# SCH_USB-Hub-with-audio-card_2025-04-09_1.net
KiCad netlist of a schematic drawn in EasyEDA
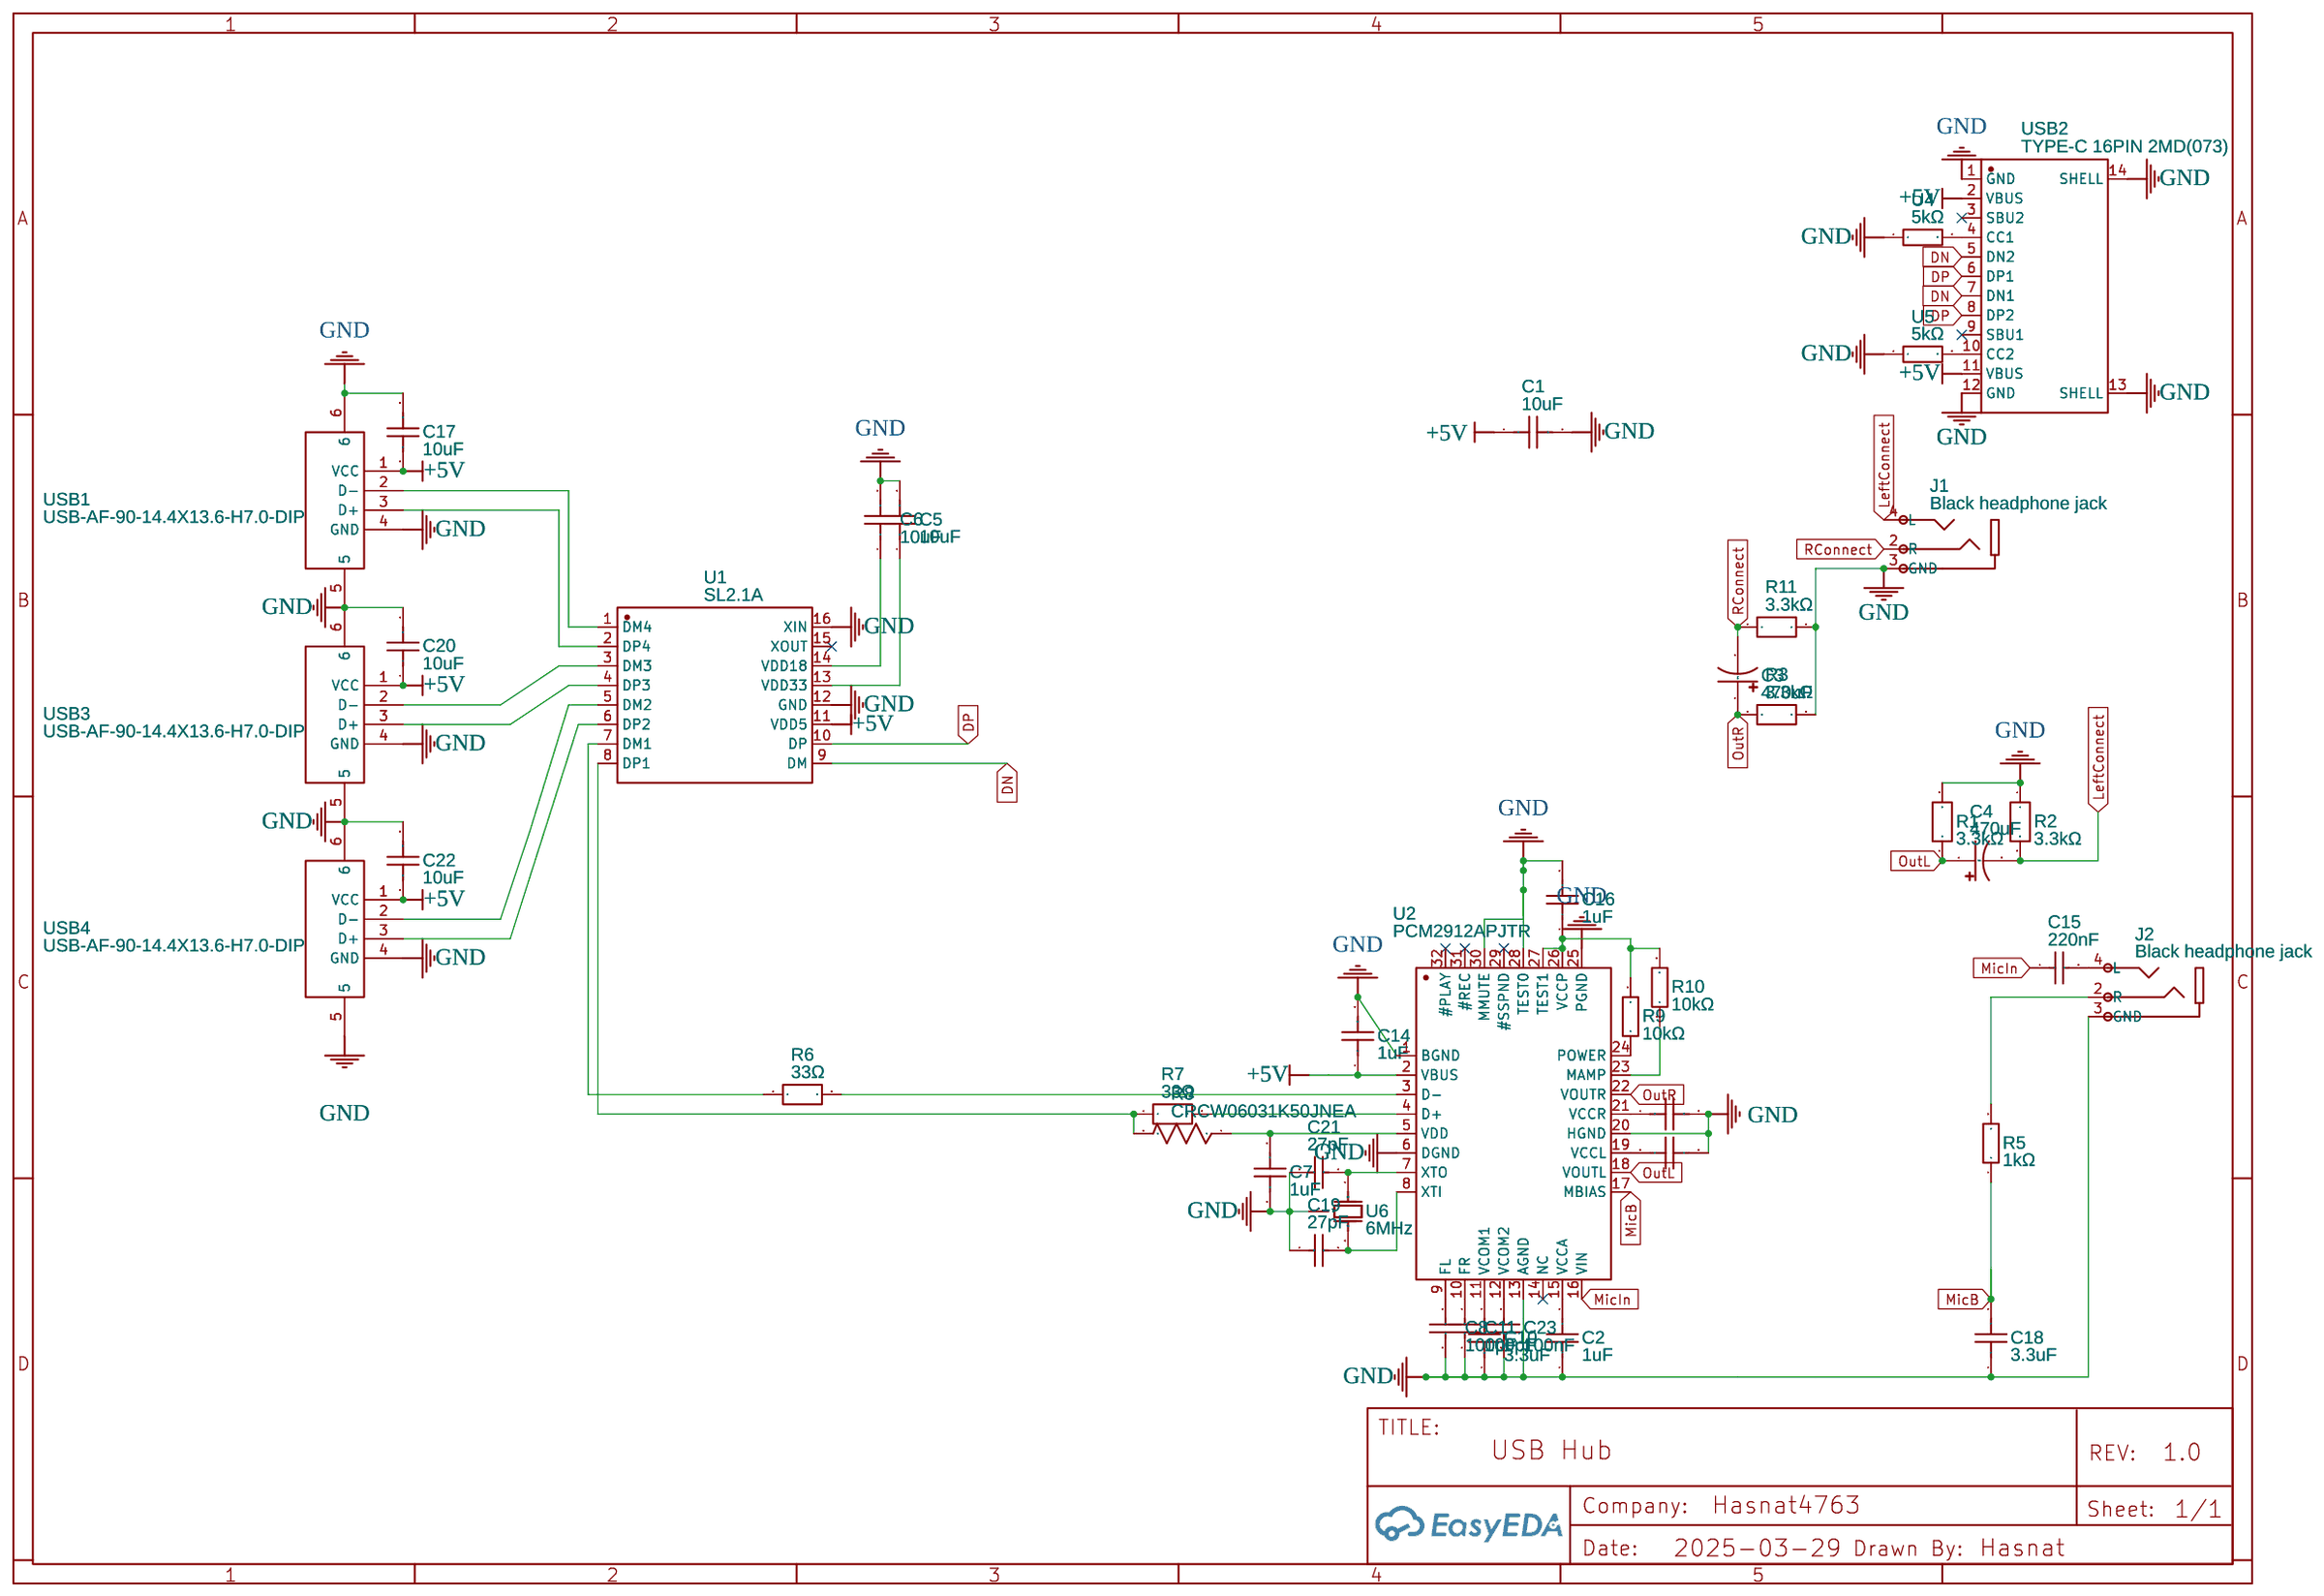
[diagram p0: schematic sheet]

(export (version "E")
  (design (tool "Eeschema 10.0.6"))
  (components
    (comp (ref "C1")
      (value "10uF")
      (fields
        (field (name "Manufacturer Part") "CL10A106KP8NNNC")
        (field (name "Manufacturer") "SAMSUNG(三星)")
      )
      (libsource (lib "") (part "CL10A106KP8NNNC_1"))
    )
    (comp (ref "C2")
      (value "1uF")
      (fields (field (name "Manufacturer Part") "CGB3B1X7R1A105K055AC") (field (name "Manufacturer") "TDK"))
      (libsource (lib "") (part "CGB3B1X7R1A105K055AC"))
    )
    (comp (ref "C3")
      (value "470uF")
      (fields (field (name "Manufacturer Part") "UKW1C471MPD") (field (name "Manufacturer") "Nichicon(尼吉康)"))
      (libsource (lib "") (part "UKW1C471MPD_1"))
    )
    (comp (ref "C4")
      (value "470uF")
      (fields (field (name "Manufacturer Part") "UKW1C471MPD") (field (name "Manufacturer") "Nichicon(尼吉康)"))
      (libsource (lib "") (part "UKW1C471MPD"))
    )
    (comp (ref "C5")
      (value "10uF")
      (fields
        (field (name "Manufacturer Part") "CL10A106KP8NNNC")
        (field (name "Manufacturer") "SAMSUNG(三星)")
      )
      (libsource (lib "") (part "CL10A106KP8NNNC"))
    )
    (comp (ref "C6")
      (value "10uF")
      (fields
        (field (name "Manufacturer Part") "CL10A106KP8NNNC")
        (field (name "Manufacturer") "SAMSUNG(三星)")
      )
      (libsource (lib "") (part "CL10A106KP8NNNC"))
    )
    (comp (ref "C7")
      (value "1uF")
      (fields
        (field (name "Manufacturer Part") "CL31B105KBHNNNE")
        (field (name "Manufacturer") "SAMSUNG(三星)")
      )
      (libsource (lib "") (part "CL31B105KBHNNNE"))
    )
    (comp (ref "C8")
      (value "100pF")
      (fields
        (field (name "Manufacturer Part") "GRM1885C1H101JA01D")
        (field (name "Manufacturer") "muRata(村田)")
      )
      (libsource (lib "") (part "GRM1885C1H101JA01D"))
    )
    (comp (ref "C10")
      (value "3.3uF")
      (fields
        (field (name "Manufacturer Part") "GRM21BR71C335KA73L")
        (field (name "Manufacturer") "muRata(村田)")
      )
      (libsource (lib "") (part "GRM21BR71C335KA73L"))
    )
    (comp (ref "C11")
      (value "100pF")
      (fields
        (field (name "Manufacturer Part") "GRM1885C1H101JA01D")
        (field (name "Manufacturer") "muRata(村田)")
      )
      (libsource (lib "") (part "GRM1885C1H101JA01D"))
    )
    (comp (ref "C12")
      (value "1uF")
      (fields
        (field (name "Manufacturer Part") "CL31B105KBHNNNE")
        (field (name "Manufacturer") "SAMSUNG(三星)")
      )
      (libsource (lib "") (part "CL31B105KBHNNNE_1"))
    )
    (comp (ref "C13")
      (value "1uF")
      (fields
        (field (name "Manufacturer Part") "CL31B105KBHNNNE")
        (field (name "Manufacturer") "SAMSUNG(三星)")
      )
      (libsource (lib "") (part "CL31B105KBHNNNE_1"))
    )
    (comp (ref "C14")
      (value "1uF")
      (fields (field (name "Manufacturer Part") "CGB3B1X7R1A105K055AC") (field (name "Manufacturer") "TDK"))
      (libsource (lib "") (part "CGB3B1X7R1A105K055AC"))
    )
    (comp (ref "C15")
      (value "220nF")
      (fields
        (field (name "Manufacturer Part") "CL05A224KA5NNNC")
        (field (name "Manufacturer") "SAMSUNG(三星)")
      )
      (libsource (lib "") (part "CL05A224KA5NNNC"))
    )
    (comp (ref "C16")
      (value "1uF")
      (fields
        (field (name "Manufacturer Part") "CL31B105KBHNNNE")
        (field (name "Manufacturer") "SAMSUNG(三星)")
      )
      (libsource (lib "") (part "CL31B105KBHNNNE"))
    )
    (comp (ref "C17")
      (value "10uF")
      (fields
        (field (name "Manufacturer Part") "CL10A106KP8NNNC")
        (field (name "Manufacturer") "SAMSUNG(三星)")
      )
      (libsource (lib "") (part "CL10A106KP8NNNC"))
    )
    (comp (ref "C18")
      (value "3.3uF")
      (fields
        (field (name "Manufacturer Part") "KVD500L335M55A0T00")
        (field (name "Manufacturer") "NCC(日本贵弥功)")
      )
      (libsource (lib "") (part "KVD500L335M55A0T00"))
    )
    (comp (ref "C19")
      (value "27pF")
      (fields
        (field (name "Manufacturer Part") "CC0805JRNPO9BN270")
        (field (name "Manufacturer") "YAGEO(国巨)")
      )
      (libsource (lib "") (part "CC0805JRNPO9BN270"))
    )
    (comp (ref "C20")
      (value "10uF")
      (fields
        (field (name "Manufacturer Part") "CL10A106KP8NNNC")
        (field (name "Manufacturer") "SAMSUNG(三星)")
      )
      (libsource (lib "") (part "CL10A106KP8NNNC"))
    )
    (comp (ref "C21")
      (value "27pF")
      (fields
        (field (name "Manufacturer Part") "CC0805JRNPO9BN270")
        (field (name "Manufacturer") "YAGEO(国巨)")
      )
      (libsource (lib "") (part "CC0805JRNPO9BN270"))
    )
    (comp (ref "C22")
      (value "10uF")
      (fields
        (field (name "Manufacturer Part") "CL10A106KP8NNNC")
        (field (name "Manufacturer") "SAMSUNG(三星)")
      )
      (libsource (lib "") (part "CL10A106KP8NNNC"))
    )
    (comp (ref "C23")
      (value "100nF")
      (fields
        (field (name "Manufacturer Part") "GRM188R71C104KA01D")
        (field (name "Manufacturer") "muRata(村田)")
      )
      (libsource (lib "") (part "GRM188R71C104KA01D"))
    )
    (comp (ref "J1")
      (value "Black headphone jack")
      (fields (field (name "Manufacturer Part") "320B直插") (field (name "Manufacturer") "BOOMELE(博穆精密)"))
      (libsource (lib "") (part "Black headphone jack"))
    )
    (comp (ref "J2")
      (value "Black headphone jack")
      (fields (field (name "Manufacturer Part") "320B直插") (field (name "Manufacturer") "BOOMELE(博穆精密)"))
      (libsource (lib "") (part "Black headphone jack"))
    )
    (comp (ref "R1")
      (value "3.3kΩ")
      (fields (field (name "Manufacturer Part") "CR-05JL7---3K3") (field (name "Manufacturer") "Viking(光颉)"))
      (libsource (lib "") (part "CR-05JL7---3K3"))
    )
    (comp (ref "R2")
      (value "3.3kΩ")
      (fields (field (name "Manufacturer Part") "CR-05JL7---3K3") (field (name "Manufacturer") "Viking(光颉)"))
      (libsource (lib "") (part "CR-05JL7---3K3_1"))
    )
    (comp (ref "R3")
      (value "3.3kΩ")
      (fields (field (name "Manufacturer Part") "CR-05JL7---3K3") (field (name "Manufacturer") "Viking(光颉)"))
      (libsource (lib "") (part "CR-05JL7---3K3_2"))
    )
    (comp (ref "R5")
      (value "1kΩ")
      (fields (field (name "Manufacturer Part") "RT0603DRD071KL") (field (name "Manufacturer") "YAGEO(国巨)"))
      (libsource (lib "") (part "RT0603DRD071KL"))
    )
    (comp (ref "R6")
      (value "33Ω")
      (fields
        (field (name "Manufacturer Part") "CRCW060333R0JNEA")
        (field (name "Manufacturer") "VISHAY(威世)")
      )
      (libsource (lib "") (part "CRCW060333R0JNEA"))
    )
    (comp (ref "R7")
      (value "33Ω")
      (fields
        (field (name "Manufacturer Part") "CRCW060333R0JNEA")
        (field (name "Manufacturer") "VISHAY(威世)")
      )
      (libsource (lib "") (part "CRCW060333R0JNEA"))
    )
    (comp (ref "R8") (value "CRCW06031K50JNEA") (libsource (lib "") (part "CRCW06031K50JNEA")))
    (comp (ref "R9")
      (value "10kΩ")
      (fields
        (field (name "Manufacturer Part") "CRCW060310K0JNEA")
        (field (name "Manufacturer") "VISHAY(威世)")
      )
      (libsource (lib "") (part "CRCW060310K0JNEA"))
    )
    (comp (ref "R10")
      (value "10kΩ")
      (fields
        (field (name "Manufacturer Part") "CRCW060310K0JNEA")
        (field (name "Manufacturer") "VISHAY(威世)")
      )
      (libsource (lib "") (part "CRCW060310K0JNEA"))
    )
    (comp (ref "R11")
      (value "3.3kΩ")
      (fields (field (name "Manufacturer Part") "CR-05JL7---3K3") (field (name "Manufacturer") "Viking(光颉)"))
      (libsource (lib "") (part "CR-05JL7---3K3_2"))
    )
    (comp (ref "U1")
      (value "SL2.1A")
      (fields (field (name "Manufacturer") "CoreChips(和芯润德)"))
      (libsource (lib "") (part "SL2.1A"))
    )
    (comp (ref "U2")
      (value "PCM2912APJTR")
      (fields (field (name "Manufacturer") "TI(德州仪器)"))
      (libsource (lib "") (part "PCM2912APJTR"))
    )
    (comp (ref "U4")
      (value "5kΩ")
      (fields (field (name "Manufacturer Part") "MFP1WSBRD52-5K") (field (name "Manufacturer") "YAGEO(国巨)"))
      (libsource (lib "") (part "MFP1WSBRD52-5K"))
    )
    (comp (ref "U5")
      (value "5kΩ")
      (fields (field (name "Manufacturer Part") "MFP1WSBRD52-5K") (field (name "Manufacturer") "YAGEO(国巨)"))
      (libsource (lib "") (part "MFP1WSBRD52-5K"))
    )
    (comp (ref "U6")
      (value "6MHz")
      (fields (field (name "Manufacturer Part") "ECS-60-18-5G3X-JGN-TR") (field (name "Manufacturer") "ECS"))
      (libsource (lib "") (part "ECS-60-18-5G3X-JGN-TR"))
    )
    (comp (ref "USB1")
      (value "USB-AF-90-14.4X13.6-H7.0-DIP")
      (fields (field (name "Manufacturer Part") "903-131A1011D10100") (field (name "Manufacturer") "精拓金"))
      (libsource (lib "") (part "USB-AF-90-14.4X13.6-H7.0-DIP"))
    )
    (comp (ref "USB2")
      (value "TYPE-C 16PIN 2MD(073)")
      (fields (field (name "Manufacturer") "SHOU HAN(首韩)"))
      (libsource (lib "") (part "TYPE-C 16PIN 2MD(073)"))
    )
    (comp (ref "USB3")
      (value "USB-AF-90-14.4X13.6-H7.0-DIP")
      (fields (field (name "Manufacturer Part") "903-131A1011D10100") (field (name "Manufacturer") "精拓金"))
      (libsource (lib "") (part "USB-AF-90-14.4X13.6-H7.0-DIP"))
    )
    (comp (ref "USB4")
      (value "USB-AF-90-14.4X13.6-H7.0-DIP")
      (fields (field (name "Manufacturer Part") "903-131A1011D10100") (field (name "Manufacturer") "精拓金"))
      (libsource (lib "") (part "USB-AF-90-14.4X13.6-H7.0-DIP"))
    )
  )
  (nets
    (net (code "1") (name "+5V") (class "Default")
      (node (ref "C1") (pin "1") (pinfunction "1_1") (pintype "unspecified"))
      (node (ref "C14") (pin "1") (pinfunction "1_1") (pintype "unspecified"))
      (node (ref "C17") (pin "1") (pinfunction "1_1") (pintype "unspecified"))
      (node (ref "C20") (pin "1") (pinfunction "1_1") (pintype "unspecified"))
      (node (ref "C22") (pin "1") (pinfunction "1_1") (pintype "unspecified"))
      (node (ref "U1") (pin "11") (pinfunction "VDD5_11") (pintype "unspecified"))
      (node (ref "U2") (pin "2") (pinfunction "VBUS_2") (pintype "unspecified"))
      (node (ref "USB1") (pin "1") (pinfunction "VCC_1") (pintype "unspecified"))
      (node (ref "USB2") (pin "11") (pinfunction "VBUS_11") (pintype "unspecified"))
      (node (ref "USB2") (pin "2") (pinfunction "VBUS_2") (pintype "unspecified"))
      (node (ref "USB3") (pin "1") (pinfunction "VCC_1") (pintype "unspecified"))
      (node (ref "USB4") (pin "1") (pinfunction "VCC_1") (pintype "unspecified"))
    )
    (net (code "2") (name "DN") (class "Default")
      (node (ref "U1") (pin "9") (pinfunction "DM_9") (pintype "unspecified"))
      (node (ref "USB2") (pin "5") (pinfunction "DN2_5") (pintype "unspecified"))
      (node (ref "USB2") (pin "7") (pinfunction "DN1_7") (pintype "unspecified"))
    )
    (net (code "3") (name "DP") (class "Default")
      (node (ref "U1") (pin "10") (pinfunction "DP_10") (pintype "unspecified"))
      (node (ref "USB2") (pin "6") (pinfunction "DP1_6") (pintype "unspecified"))
      (node (ref "USB2") (pin "8") (pinfunction "DP2_8") (pintype "unspecified"))
    )
    (net (code "4") (name "GND") (class "Default")
      (node (ref "C1") (pin "2") (pinfunction "2_2") (pintype "unspecified"))
      (node (ref "C10") (pin "1") (pinfunction "1_1") (pintype "unspecified"))
      (node (ref "C11") (pin "1") (pinfunction "1_1") (pintype "input"))
      (node (ref "C12") (pin "2") (pinfunction "2_2") (pintype "unspecified"))
      (node (ref "C13") (pin "2") (pinfunction "2_2") (pintype "unspecified"))
      (node (ref "C14") (pin "2") (pinfunction "2_2") (pintype "unspecified"))
      (node (ref "C16") (pin "2") (pinfunction "2_2") (pintype "unspecified"))
      (node (ref "C17") (pin "2") (pinfunction "2_2") (pintype "unspecified"))
      (node (ref "C18") (pin "1") (pinfunction "1_1") (pintype "unspecified"))
      (node (ref "C19") (pin "1") (pinfunction "1_1") (pintype "input"))
      (node (ref "C2") (pin "1") (pinfunction "1_1") (pintype "unspecified"))
      (node (ref "C20") (pin "2") (pinfunction "2_2") (pintype "unspecified"))
      (node (ref "C21") (pin "1") (pinfunction "1_1") (pintype "input"))
      (node (ref "C22") (pin "2") (pinfunction "2_2") (pintype "unspecified"))
      (node (ref "C23") (pin "1") (pinfunction "1_1") (pintype "input"))
      (node (ref "C5") (pin "2") (pinfunction "2_2") (pintype "unspecified"))
      (node (ref "C6") (pin "2") (pinfunction "2_2") (pintype "unspecified"))
      (node (ref "C7") (pin "1") (pinfunction "1_1") (pintype "unspecified"))
      (node (ref "C8") (pin "1") (pinfunction "1_1") (pintype "input"))
      (node (ref "J1") (pin "3") (pinfunction "GND_3") (pintype "input"))
      (node (ref "J2") (pin "3") (pinfunction "GND_3") (pintype "input"))
      (node (ref "R1") (pin "2") (pinfunction "2_2") (pintype "unspecified"))
      (node (ref "R11") (pin "2") (pinfunction "2_2") (pintype "unspecified"))
      (node (ref "R2") (pin "1") (pinfunction "1_1") (pintype "unspecified"))
      (node (ref "R3") (pin "2") (pinfunction "2_2") (pintype "unspecified"))
      (node (ref "U1") (pin "12") (pinfunction "GND_12") (pintype "unspecified"))
      (node (ref "U1") (pin "16") (pinfunction "XIN_16") (pintype "unspecified"))
      (node (ref "U2") (pin "1") (pinfunction "BGND_1") (pintype "unspecified"))
      (node (ref "U2") (pin "13") (pinfunction "AGND_13") (pintype "unspecified"))
      (node (ref "U2") (pin "20") (pinfunction "HGND_20") (pintype "unspecified"))
      (node (ref "U2") (pin "25") (pinfunction "PGND_25") (pintype "unspecified"))
      (node (ref "U2") (pin "28") (pinfunction "TEST0_28") (pintype "unspecified"))
      (node (ref "U2") (pin "30") (pinfunction "MMUTE_30") (pintype "unspecified"))
      (node (ref "U2") (pin "6") (pinfunction "DGND_6") (pintype "unspecified"))
      (node (ref "U4") (pin "1") (pinfunction "1_1") (pintype "unspecified"))
      (node (ref "U5") (pin "1") (pinfunction "1_1") (pintype "unspecified"))
      (node (ref "U6") (pin "3") (pinfunction "GND_3") (pintype "input"))
      (node (ref "USB1") (pin "4") (pinfunction "GND_4") (pintype "unspecified"))
      (node (ref "USB1") (pin "5") (pinfunction "5_5") (pintype "unspecified"))
      (node (ref "USB1") (pin "6") (pinfunction "6_6") (pintype "unspecified"))
      (node (ref "USB2") (pin "1") (pinfunction "GND_1") (pintype "unspecified"))
      (node (ref "USB2") (pin "12") (pinfunction "GND_12") (pintype "unspecified"))
      (node (ref "USB2") (pin "13") (pinfunction "SHELL_13") (pintype "unspecified"))
      (node (ref "USB2") (pin "14") (pinfunction "SHELL_14") (pintype "unspecified"))
      (node (ref "USB3") (pin "4") (pinfunction "GND_4") (pintype "unspecified"))
      (node (ref "USB3") (pin "5") (pinfunction "5_5") (pintype "unspecified"))
      (node (ref "USB3") (pin "6") (pinfunction "6_6") (pintype "unspecified"))
      (node (ref "USB4") (pin "4") (pinfunction "GND_4") (pintype "unspecified"))
      (node (ref "USB4") (pin "5") (pinfunction "5_5") (pintype "unspecified"))
      (node (ref "USB4") (pin "6") (pinfunction "6_6") (pintype "unspecified"))
    )
    (net (code "5") (name "LeftConnect") (class "Default")
      (node (ref "C4") (pin "2") (pinfunction "2_2") (pintype "unspecified"))
      (node (ref "J1") (pin "4") (pinfunction "L_4") (pintype "input"))
      (node (ref "R2") (pin "2") (pinfunction "2_2") (pintype "unspecified"))
    )
    (net (code "6") (name "MicB") (class "Default")
      (node (ref "C18") (pin "2") (pinfunction "2_2") (pintype "unspecified"))
      (node (ref "R5") (pin "1") (pinfunction "1_1") (pintype "unspecified"))
      (node (ref "U2") (pin "17") (pinfunction "MBIAS_17") (pintype "unspecified"))
    )
    (net (code "7") (name "MicIn") (class "Default")
      (node (ref "C15") (pin "1") (pinfunction "1_1") (pintype "input"))
      (node (ref "U2") (pin "16") (pinfunction "VIN_16") (pintype "unspecified"))
    )
    (net (code "8") (name "Net-(J2-L)") (class "Default")
      (node (ref "C15") (pin "2") (pinfunction "2_2") (pintype "input"))
      (node (ref "J2") (pin "4") (pinfunction "L_4") (pintype "input"))
    )
    (net (code "9") (name "Net-(J2-R)") (class "Default")
      (node (ref "J2") (pin "2") (pinfunction "R_2") (pintype "input"))
      (node (ref "R5") (pin "2") (pinfunction "2_2") (pintype "unspecified"))
    )
    (net (code "10") (name "Net-(U1-DM1)") (class "Default")
      (node (ref "R6") (pin "1") (pinfunction "1_1") (pintype "unspecified"))
      (node (ref "U1") (pin "7") (pinfunction "DM1_7") (pintype "unspecified"))
    )
    (net (code "11") (name "Net-(U1-DM2)") (class "Default")
      (node (ref "U1") (pin "5") (pinfunction "DM2_5") (pintype "unspecified"))
      (node (ref "USB4") (pin "2") (pinfunction "D-_2") (pintype "unspecified"))
    )
    (net (code "12") (name "Net-(U1-DM3)") (class "Default")
      (node (ref "U1") (pin "3") (pinfunction "DM3_3") (pintype "unspecified"))
      (node (ref "USB3") (pin "2") (pinfunction "D-_2") (pintype "unspecified"))
    )
    (net (code "13") (name "Net-(U1-DM4)") (class "Default")
      (node (ref "U1") (pin "1") (pinfunction "DM4_1") (pintype "unspecified"))
      (node (ref "USB1") (pin "2") (pinfunction "D-_2") (pintype "unspecified"))
    )
    (net (code "14") (name "Net-(U1-DP1)") (class "Default")
      (node (ref "R7") (pin "1") (pinfunction "1_1") (pintype "unspecified"))
      (node (ref "R8") (pin "2") (pinfunction "2_2") (pintype "unspecified"))
      (node (ref "U1") (pin "8") (pinfunction "DP1_8") (pintype "unspecified"))
    )
    (net (code "15") (name "Net-(U1-DP2)") (class "Default")
      (node (ref "U1") (pin "6") (pinfunction "DP2_6") (pintype "unspecified"))
      (node (ref "USB4") (pin "3") (pinfunction "D+_3") (pintype "unspecified"))
    )
    (net (code "16") (name "Net-(U1-DP3)") (class "Default")
      (node (ref "U1") (pin "4") (pinfunction "DP3_4") (pintype "unspecified"))
      (node (ref "USB3") (pin "3") (pinfunction "D+_3") (pintype "unspecified"))
    )
    (net (code "17") (name "Net-(U1-DP4)") (class "Default")
      (node (ref "U1") (pin "2") (pinfunction "DP4_2") (pintype "unspecified"))
      (node (ref "USB1") (pin "3") (pinfunction "D+_3") (pintype "unspecified"))
    )
    (net (code "18") (name "Net-(U1-VDD18)") (class "Default")
      (node (ref "C6") (pin "1") (pinfunction "1_1") (pintype "unspecified"))
      (node (ref "U1") (pin "14") (pinfunction "VDD18_14") (pintype "unspecified"))
    )
    (net (code "19") (name "Net-(U1-VDD33)") (class "Default")
      (node (ref "C5") (pin "1") (pinfunction "1_1") (pintype "unspecified"))
      (node (ref "U1") (pin "13") (pinfunction "VDD33_13") (pintype "unspecified"))
    )
    (net (code "20") (name "Net-(U2-D+)") (class "Default")
      (node (ref "R7") (pin "2") (pinfunction "2_2") (pintype "unspecified"))
      (node (ref "U2") (pin "4") (pinfunction "D+_4") (pintype "unspecified"))
    )
    (net (code "21") (name "Net-(U2-D-)") (class "Default")
      (node (ref "R6") (pin "2") (pinfunction "2_2") (pintype "unspecified"))
      (node (ref "U2") (pin "3") (pinfunction "D-_3") (pintype "unspecified"))
    )
    (net (code "22") (name "Net-(U2-FL)") (class "Default")
      (node (ref "C8") (pin "2") (pinfunction "2_2") (pintype "input"))
      (node (ref "U2") (pin "9") (pinfunction "FL_9") (pintype "unspecified"))
    )
    (net (code "23") (name "Net-(U2-FR)") (class "Default")
      (node (ref "C11") (pin "2") (pinfunction "2_2") (pintype "input"))
      (node (ref "U2") (pin "10") (pinfunction "FR_10") (pintype "unspecified"))
    )
    (net (code "24") (name "Net-(U2-MAMP)") (class "Default")
      (node (ref "R10") (pin "1") (pinfunction "1_1") (pintype "unspecified"))
      (node (ref "U2") (pin "23") (pinfunction "MAMP_23") (pintype "unspecified"))
    )
    (net (code "25") (name "Net-(U2-POWER)") (class "Default")
      (node (ref "R9") (pin "1") (pinfunction "1_1") (pintype "unspecified"))
      (node (ref "U2") (pin "24") (pinfunction "POWER_24") (pintype "unspecified"))
    )
    (net (code "26") (name "Net-(U2-TEST1)") (class "Default")
      (node (ref "C16") (pin "1") (pinfunction "1_1") (pintype "unspecified"))
      (node (ref "R10") (pin "2") (pinfunction "2_2") (pintype "unspecified"))
      (node (ref "R9") (pin "2") (pinfunction "2_2") (pintype "unspecified"))
      (node (ref "U2") (pin "26") (pinfunction "VCCP_26") (pintype "unspecified"))
      (node (ref "U2") (pin "27") (pinfunction "TEST1_27") (pintype "unspecified"))
    )
    (net (code "27") (name "Net-(U2-VCCA)") (class "Default")
      (node (ref "C2") (pin "2") (pinfunction "2_2") (pintype "unspecified"))
      (node (ref "U2") (pin "15") (pinfunction "VCCA_15") (pintype "unspecified"))
    )
    (net (code "28") (name "Net-(U2-VCCL)") (class "Default")
      (node (ref "C13") (pin "1") (pinfunction "1_1") (pintype "unspecified"))
      (node (ref "U2") (pin "19") (pinfunction "VCCL_19") (pintype "unspecified"))
    )
    (net (code "29") (name "Net-(U2-VCCR)") (class "Default")
      (node (ref "C12") (pin "1") (pinfunction "1_1") (pintype "unspecified"))
      (node (ref "U2") (pin "21") (pinfunction "VCCR_21") (pintype "unspecified"))
    )
    (net (code "30") (name "Net-(U2-VCOM1)") (class "Default")
      (node (ref "C10") (pin "2") (pinfunction "2_2") (pintype "unspecified"))
      (node (ref "U2") (pin "11") (pinfunction "VCOM1_11") (pintype "unspecified"))
    )
    (net (code "31") (name "Net-(U2-VCOM2)") (class "Default")
      (node (ref "C23") (pin "2") (pinfunction "2_2") (pintype "input"))
      (node (ref "U2") (pin "12") (pinfunction "VCOM2_12") (pintype "unspecified"))
    )
    (net (code "32") (name "Net-(U2-VDD)") (class "Default")
      (node (ref "C7") (pin "2") (pinfunction "2_2") (pintype "unspecified"))
      (node (ref "R8") (pin "1") (pinfunction "1_1") (pintype "unspecified"))
      (node (ref "U2") (pin "5") (pinfunction "VDD_5") (pintype "unspecified"))
    )
    (net (code "33") (name "Net-(U2-XTI)") (class "Default")
      (node (ref "C19") (pin "2") (pinfunction "2_2") (pintype "input"))
      (node (ref "U2") (pin "8") (pinfunction "XTI_8") (pintype "unspecified"))
      (node (ref "U6") (pin "2") (pinfunction "Out/In_2") (pintype "input"))
    )
    (net (code "34") (name "Net-(U2-XTO)") (class "Default")
      (node (ref "C21") (pin "2") (pinfunction "2_2") (pintype "input"))
      (node (ref "U2") (pin "7") (pinfunction "XTO_7") (pintype "unspecified"))
      (node (ref "U6") (pin "1") (pinfunction "In/Out_1") (pintype "input"))
    )
    (net (code "35") (name "Net-(USB2-CC1)") (class "Default")
      (node (ref "U4") (pin "2") (pinfunction "2_2") (pintype "unspecified"))
      (node (ref "USB2") (pin "4") (pinfunction "CC1_4") (pintype "unspecified"))
    )
    (net (code "36") (name "Net-(USB2-CC2)") (class "Default")
      (node (ref "U5") (pin "2") (pinfunction "2_2") (pintype "unspecified"))
      (node (ref "USB2") (pin "10") (pinfunction "CC2_10") (pintype "unspecified"))
    )
    (net (code "37") (name "OutL") (class "Default")
      (node (ref "C4") (pin "1") (pinfunction "1_1") (pintype "unspecified"))
      (node (ref "R1") (pin "1") (pinfunction "1_1") (pintype "unspecified"))
      (node (ref "U2") (pin "18") (pinfunction "VOUTL_18") (pintype "unspecified"))
    )
    (net (code "38") (name "OutR") (class "Default")
      (node (ref "C3") (pin "1") (pinfunction "1_1") (pintype "unspecified"))
      (node (ref "R3") (pin "1") (pinfunction "1_1") (pintype "unspecified"))
      (node (ref "U2") (pin "22") (pinfunction "VOUTR_22") (pintype "unspecified"))
    )
    (net (code "39") (name "RConnect") (class "Default")
      (node (ref "C3") (pin "2") (pinfunction "2_2") (pintype "unspecified"))
      (node (ref "J1") (pin "2") (pinfunction "R_2") (pintype "input"))
      (node (ref "R11") (pin "1") (pinfunction "1_1") (pintype "unspecified"))
    )
    (net (code "40") (name "unconnected-(U1-XOUT-Pad15)") (class "Default")
      (node (ref "U1") (pin "15") (pinfunction "XOUT_15") (pintype "unspecified+no_connect"))
    )
    (net (code "41") (name "unconnected-(U2-#PLAY-Pad32)") (class "Default")
      (node (ref "U2") (pin "32") (pinfunction "#PLAY_32") (pintype "unspecified+no_connect"))
    )
    (net (code "42") (name "unconnected-(U2-#REC-Pad31)") (class "Default")
      (node (ref "U2") (pin "31") (pinfunction "#REC_31") (pintype "unspecified+no_connect"))
    )
    (net (code "43") (name "unconnected-(U2-#SSPND-Pad29)") (class "Default")
      (node (ref "U2") (pin "29") (pinfunction "#SSPND_29") (pintype "unspecified+no_connect"))
    )
    (net (code "44") (name "unconnected-(U2-NC-Pad14)") (class "Default")
      (node (ref "U2") (pin "14") (pinfunction "NC_14") (pintype "unspecified+no_connect"))
    )
    (net (code "45") (name "unconnected-(USB2-SBU1-Pad9)") (class "Default")
      (node (ref "USB2") (pin "9") (pinfunction "SBU1_9") (pintype "unspecified+no_connect"))
    )
    (net (code "46") (name "unconnected-(USB2-SBU2-Pad3)") (class "Default")
      (node (ref "USB2") (pin "3") (pinfunction "SBU2_3") (pintype "unspecified+no_connect"))
    )
  )
)
